# board.net
KiCad netlist of a schematic drawn in EAGLE
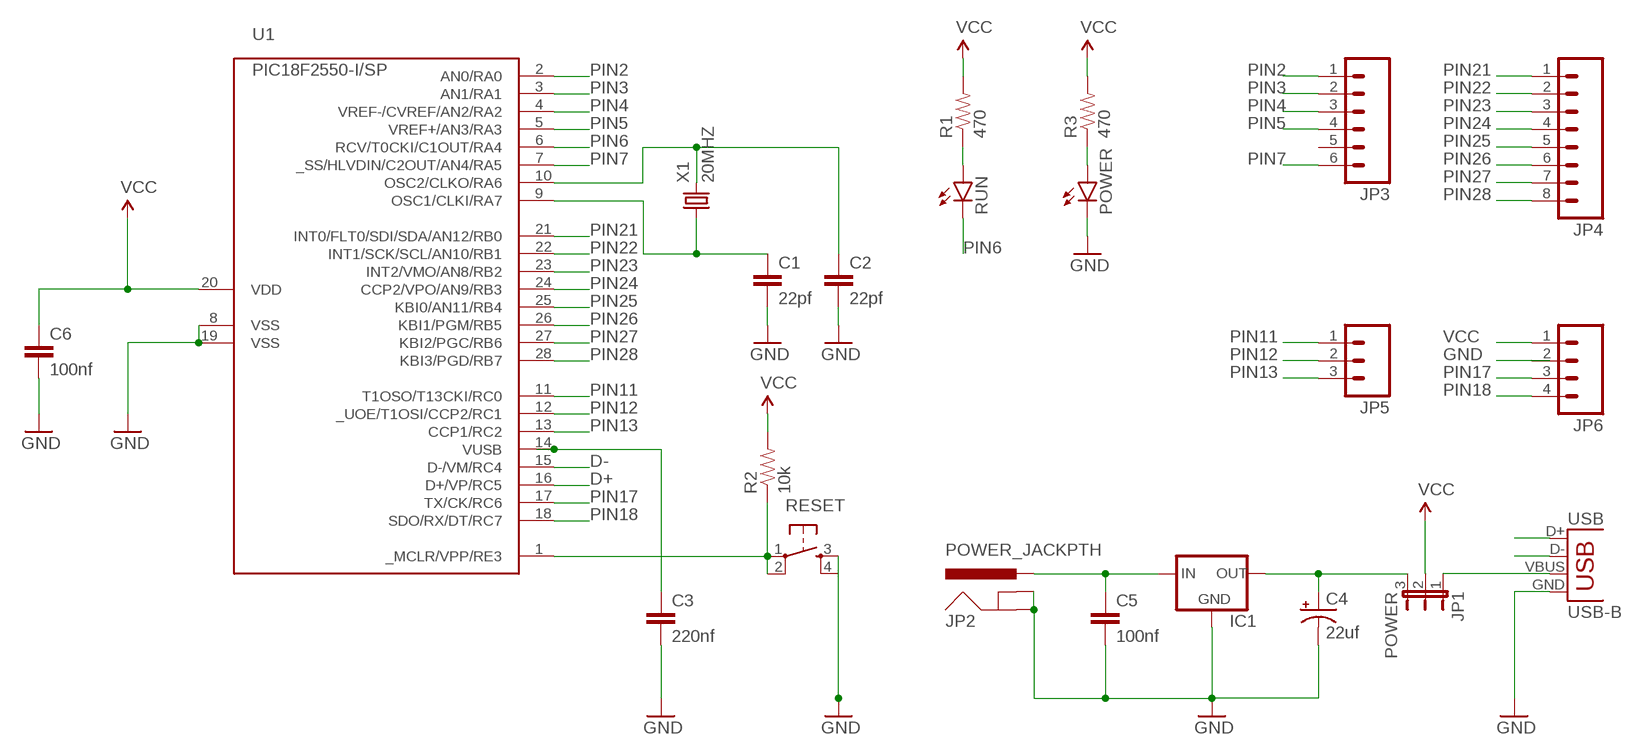
[diagram p0: schematic, sheet 1]

(export (version "E")
  (design (tool "Eeschema 10.0.6"))
  (components
    (comp (ref "C1")
      (value "22pf")
      (footprint "eagle-import:CAP-PTH-SMALL-KIT")
      (libsource (lib "eagle-import") (part "0.1UF-50V-20%(PTH)KIT-EZ"))
    )
    (comp (ref "C2")
      (value "22pf")
      (footprint "eagle-import:CAP-PTH-SMALL-KIT")
      (libsource (lib "eagle-import") (part "0.1UF-50V-20%(PTH)KIT-EZ"))
    )
    (comp (ref "C3")
      (value "220nf")
      (footprint "eagle-import:C050-050X075")
      (libsource (lib "eagle-import") (part "C-EU050-050X075"))
    )
    (comp (ref "C4")
      (value "22uf")
      (footprint "eagle-import:CPOL-RADIAL-10UF-25V-KIT")
      (libsource (lib "eagle-import") (part "10UF-25V-20%(PTH)KIT"))
    )
    (comp (ref "C5")
      (value "100nf")
      (footprint "eagle-import:C050-050X075")
      (libsource (lib "eagle-import") (part "C-EU050-050X075"))
    )
    (comp (ref "C6")
      (value "100nf")
      (footprint "eagle-import:C050-050X075")
      (libsource (lib "eagle-import") (part "C-EU050-050X075"))
    )
    (comp (ref "IC1")
      (value "78XXL")
      (footprint "eagle-import:78XXL")
      (libsource (lib "eagle-import") (part "78XXL"))
    )
    (comp (ref "JP1")
      (value "POWER")
      (footprint "eagle-import:JP2")
      (libsource (lib "eagle-import") (part "JP2E"))
    )
    (comp (ref "JP2")
      (value "POWER_JACKPTH")
      (footprint "eagle-import:POWER_JACK_PTH")
      (libsource (lib "eagle-import") (part "POWER_JACKPTH"))
    )
    (comp (ref "JP3")
      (value "M06NO_SILK_YES_STOP")
      (footprint "eagle-import:1X06_NO_SILK_YES_STOP")
      (libsource (lib "eagle-import") (part "M06NO_SILK_YES_STOP"))
    )
    (comp (ref "JP4")
      (value "M08NO_SILK_FEMALE_PTH")
      (footprint "eagle-import:1X08_NO_SILK")
      (libsource (lib "eagle-import") (part "M08NO_SILK_FEMALE_PTH"))
    )
    (comp (ref "JP5")
      (value "M031X03_NO_SILK")
      (footprint "eagle-import:1X03_NO_SILK")
      (libsource (lib "eagle-import") (part "M031X03_NO_SILK"))
    )
    (comp (ref "JP6")
      (value "M04NO_SILK_ALL_ROUND")
      (footprint "eagle-import:1X04_NO_SILK_ALL_ROUND")
      (libsource (lib "eagle-import") (part "M04NO_SILK_ALL_ROUND"))
    )
    (comp (ref "POWER")
      (value "LED3MM")
      (footprint "eagle-import:LED3MM")
      (libsource (lib "eagle-import") (part "LED3MM"))
    )
    (comp (ref "R1")
      (value "470")
      (footprint "eagle-import:AXIAL-0.4")
      (libsource (lib "eagle-import") (part "RESISTORPTH-1/4W"))
    )
    (comp (ref "R2")
      (value "10k")
      (footprint "eagle-import:AXIAL-0.4")
      (libsource (lib "eagle-import") (part "RESISTORPTH-1/4W"))
    )
    (comp (ref "R3")
      (value "470")
      (footprint "eagle-import:AXIAL-0.4")
      (libsource (lib "eagle-import") (part "RESISTORPTH-1/4W"))
    )
    (comp (ref "RESET")
      (value "TAC_SWITCHPTH")
      (footprint "eagle-import:TACTILE-PTH")
      (libsource (lib "eagle-import") (part "TAC_SWITCHPTH"))
    )
    (comp (ref "RUN")
      (value "LED3MM")
      (footprint "eagle-import:LED3MM")
      (libsource (lib "eagle-import") (part "LED3MM"))
    )
    (comp (ref "U1")
      (value "PIC18F2550-I/SP")
      (footprint "eagle-import:DIL28-3")
      (libsource (lib "eagle-import") (part "PIC182550-I/SPF"))
    )
    (comp (ref "USB")
      (value "USB-B")
      (footprint "eagle-import:USB-B-PTH")
      (libsource (lib "eagle-import") (part "USBPTH"))
    )
    (comp (ref "X1")
      (value "20MHZ")
      (footprint "eagle-import:HC49")
      (libsource (lib "eagle-import") (part "CRYSTALS-NOGND-HC49"))
    )
  )
  (nets
    (net (code "1") (name "/D+") (class "Default")
      (node (ref "U1") (pin "16") (pinfunction "D+/VP/RC5_16") (pintype "bidirectional"))
      (node (ref "USB") (pin "D+") (pinfunction "D+_D+") (pintype "bidirectional"))
    )
    (net (code "2") (name "/D-") (class "Default")
      (node (ref "U1") (pin "15") (pinfunction "D-/VM/RC4_15") (pintype "bidirectional"))
      (node (ref "USB") (pin "D-") (pinfunction "D-_D-") (pintype "bidirectional"))
    )
    (net (code "3") (name "/PIN2") (class "Default")
      (node (ref "JP3") (pin "1") (pinfunction "1_1") (pintype "passive"))
      (node (ref "U1") (pin "2") (pinfunction "AN0/RA0_2") (pintype "bidirectional"))
    )
    (net (code "4") (name "/PIN3") (class "Default")
      (node (ref "JP3") (pin "2") (pinfunction "2_2") (pintype "passive"))
      (node (ref "U1") (pin "3") (pinfunction "AN1/RA1_3") (pintype "bidirectional"))
    )
    (net (code "5") (name "/PIN4") (class "Default")
      (node (ref "JP3") (pin "3") (pinfunction "3_3") (pintype "passive"))
      (node (ref "U1") (pin "4") (pinfunction "VREF-/CVREF/AN2/RA2_4") (pintype "bidirectional"))
    )
    (net (code "6") (name "/PIN5") (class "Default")
      (node (ref "JP3") (pin "4") (pinfunction "4_4") (pintype "passive"))
      (node (ref "U1") (pin "5") (pinfunction "VREF+/AN3/RA3_5") (pintype "bidirectional"))
    )
    (net (code "7") (name "/PIN6") (class "Default")
      (node (ref "RUN") (pin "K") (pinfunction "C_K") (pintype "passive"))
      (node (ref "U1") (pin "6") (pinfunction "RCV/T0CKI/C1OUT/RA4_6") (pintype "bidirectional"))
    )
    (net (code "8") (name "/PIN7") (class "Default")
      (node (ref "JP3") (pin "6") (pinfunction "6_6") (pintype "passive"))
      (node (ref "U1") (pin "7") (pinfunction "_SS/HLVDIN/C2OUT/AN4/RA5_7") (pintype "bidirectional"))
    )
    (net (code "9") (name "/PIN11") (class "Default")
      (node (ref "JP5") (pin "1") (pinfunction "1_1") (pintype "passive"))
      (node (ref "U1") (pin "11") (pinfunction "T1OSO/T13CKI/RC0_11") (pintype "bidirectional"))
    )
    (net (code "10") (name "/PIN12") (class "Default")
      (node (ref "JP5") (pin "2") (pinfunction "2_2") (pintype "passive"))
      (node (ref "U1") (pin "12") (pinfunction "_UOE/T1OSI/CCP2/RC1_12") (pintype "bidirectional"))
    )
    (net (code "11") (name "/PIN13") (class "Default")
      (node (ref "JP5") (pin "3") (pinfunction "3_3") (pintype "passive"))
      (node (ref "U1") (pin "13") (pinfunction "CCP1/RC2_13") (pintype "bidirectional"))
    )
    (net (code "12") (name "/PIN17") (class "Default")
      (node (ref "JP6") (pin "3") (pinfunction "3_3") (pintype "passive"))
      (node (ref "U1") (pin "17") (pinfunction "TX/CK/RC6_17") (pintype "bidirectional"))
    )
    (net (code "13") (name "/PIN18") (class "Default")
      (node (ref "JP6") (pin "4") (pinfunction "4_4") (pintype "passive"))
      (node (ref "U1") (pin "18") (pinfunction "SDO/RX/DT/RC7_18") (pintype "bidirectional"))
    )
    (net (code "14") (name "/PIN21") (class "Default")
      (node (ref "JP4") (pin "1") (pinfunction "1_1") (pintype "passive"))
      (node (ref "U1") (pin "21") (pinfunction "INT0/FLT0/SDI/SDA/AN12/RB0_21") (pintype "bidirectional"))
    )
    (net (code "15") (name "/PIN22") (class "Default")
      (node (ref "JP4") (pin "2") (pinfunction "2_2") (pintype "passive"))
      (node (ref "U1") (pin "22") (pinfunction "INT1/SCK/SCL/AN10/RB1_22") (pintype "bidirectional"))
    )
    (net (code "16") (name "/PIN23") (class "Default")
      (node (ref "JP4") (pin "3") (pinfunction "3_3") (pintype "passive"))
      (node (ref "U1") (pin "23") (pinfunction "INT2/VMO/AN8/RB2_23") (pintype "bidirectional"))
    )
    (net (code "17") (name "/PIN24") (class "Default")
      (node (ref "JP4") (pin "4") (pinfunction "4_4") (pintype "passive"))
      (node (ref "U1") (pin "24") (pinfunction "CCP2/VPO/AN9/RB3_24") (pintype "bidirectional"))
    )
    (net (code "18") (name "/PIN25") (class "Default")
      (node (ref "JP4") (pin "5") (pinfunction "5_5") (pintype "passive"))
      (node (ref "U1") (pin "25") (pinfunction "KBI0/AN11/RB4_25") (pintype "bidirectional"))
    )
    (net (code "19") (name "/PIN26") (class "Default")
      (node (ref "JP4") (pin "6") (pinfunction "6_6") (pintype "passive"))
      (node (ref "U1") (pin "26") (pinfunction "KBI1/PGM/RB5_26") (pintype "bidirectional"))
    )
    (net (code "20") (name "/PIN27") (class "Default")
      (node (ref "JP4") (pin "7") (pinfunction "7_7") (pintype "passive"))
      (node (ref "U1") (pin "27") (pinfunction "KBI2/PGC/RB6_27") (pintype "bidirectional"))
    )
    (net (code "21") (name "/PIN28") (class "Default")
      (node (ref "JP4") (pin "8") (pinfunction "8_8") (pintype "passive"))
      (node (ref "U1") (pin "28") (pinfunction "KBI3/PGD/RB7_28") (pintype "bidirectional"))
    )
    (net (code "22") (name "GND") (class "Default")
      (node (ref "C1") (pin "2") (pinfunction "2_2") (pintype "passive"))
      (node (ref "C2") (pin "2") (pinfunction "2_2") (pintype "passive"))
      (node (ref "C3") (pin "2") (pinfunction "2_2") (pintype "passive"))
      (node (ref "C4") (pin "2") (pinfunction "-_2") (pintype "passive"))
      (node (ref "C5") (pin "2") (pinfunction "2_2") (pintype "passive"))
      (node (ref "C6") (pin "2") (pinfunction "2_2") (pintype "passive"))
      (node (ref "IC1") (pin "GND") (pinfunction "GND_GND") (pintype "input"))
      (node (ref "JP2") (pin "GND") (pinfunction "GND_GND") (pintype "bidirectional"))
      (node (ref "JP2") (pin "GNDBREAK") (pinfunction "GNDBREAK_GNDBREAK") (pintype "bidirectional"))
      (node (ref "POWER") (pin "K") (pinfunction "C_K") (pintype "passive"))
      (node (ref "RESET") (pin "3") (pinfunction "3_3") (pintype "passive"))
      (node (ref "RESET") (pin "4") (pinfunction "4_4") (pintype "passive"))
      (node (ref "U1") (pin "19") (pinfunction "VSS_19") (pintype "power_in"))
      (node (ref "U1") (pin "8") (pinfunction "VSS_8") (pintype "power_in"))
      (node (ref "USB") (pin "GND") (pinfunction "GND_GND") (pintype "bidirectional"))
    )
    (net (code "23") (name "Net-(C4-+)") (class "Default")
      (node (ref "C4") (pin "1") (pinfunction "+_1") (pintype "passive"))
      (node (ref "IC1") (pin "OUT") (pinfunction "OUT_OUT") (pintype "passive"))
      (node (ref "JP1") (pin "3") (pinfunction "3_3") (pintype "passive"))
    )
    (net (code "24") (name "Net-(C5-Pad1)") (class "Default")
      (node (ref "C5") (pin "1") (pinfunction "1_1") (pintype "passive"))
      (node (ref "IC1") (pin "IN") (pinfunction "IN_IN") (pintype "input"))
      (node (ref "JP2") (pin "PWR") (pinfunction "PWR_PWR") (pintype "bidirectional"))
    )
    (net (code "25") (name "Net-(JP1-Pad1)") (class "Default")
      (node (ref "JP1") (pin "1") (pinfunction "1_1") (pintype "passive"))
      (node (ref "USB") (pin "VBUS") (pinfunction "VBUS_VBUS") (pintype "bidirectional"))
    )
    (net (code "26") (name "Net-(R1-1)") (class "Default")
      (node (ref "R1") (pin "P$1") (pinfunction "1_P$1") (pintype "passive"))
      (node (ref "RUN") (pin "A") (pinfunction "A_A") (pintype "passive"))
    )
    (net (code "27") (name "Net-(R2-1)") (class "Default")
      (node (ref "R2") (pin "P$1") (pinfunction "1_P$1") (pintype "passive"))
      (node (ref "RESET") (pin "1") (pinfunction "1_1") (pintype "passive"))
      (node (ref "RESET") (pin "2") (pinfunction "2_2") (pintype "passive"))
      (node (ref "U1") (pin "1") (pinfunction "_MCLR/VPP/RE3_1") (pintype "input"))
    )
    (net (code "28") (name "Net-(R3-1)") (class "Default")
      (node (ref "POWER") (pin "A") (pinfunction "A_A") (pintype "passive"))
      (node (ref "R3") (pin "P$1") (pinfunction "1_P$1") (pintype "passive"))
    )
    (net (code "29") (name "Net-(U1-OSC1{slash}CLKI{slash}RA7)") (class "Default")
      (node (ref "C1") (pin "1") (pinfunction "1_1") (pintype "passive"))
      (node (ref "U1") (pin "9") (pinfunction "OSC1/CLKI/RA7_9") (pintype "bidirectional"))
      (node (ref "X1") (pin "1") (pinfunction "1_1") (pintype "passive"))
    )
    (net (code "30") (name "Net-(U1-OSC2{slash}CLKO{slash}RA6)") (class "Default")
      (node (ref "C2") (pin "1") (pinfunction "1_1") (pintype "passive"))
      (node (ref "U1") (pin "10") (pinfunction "OSC2/CLKO/RA6_10") (pintype "bidirectional"))
      (node (ref "X1") (pin "2") (pinfunction "2_2") (pintype "passive"))
    )
    (net (code "31") (name "Net-(U1-VUSB)") (class "Default")
      (node (ref "C3") (pin "1") (pinfunction "1_1") (pintype "passive"))
      (node (ref "U1") (pin "14") (pinfunction "VUSB_14") (pintype "bidirectional"))
    )
    (net (code "32") (name "VCC") (class "Default")
      (node (ref "C6") (pin "1") (pinfunction "1_1") (pintype "passive"))
      (node (ref "JP1") (pin "2") (pinfunction "2_2") (pintype "passive"))
      (node (ref "JP6") (pin "1") (pinfunction "1_1") (pintype "passive"))
      (node (ref "R1") (pin "P$2") (pinfunction "2_P$2") (pintype "passive"))
      (node (ref "R2") (pin "P$2") (pinfunction "2_P$2") (pintype "passive"))
      (node (ref "R3") (pin "P$2") (pinfunction "2_P$2") (pintype "passive"))
      (node (ref "U1") (pin "20") (pinfunction "VDD_20") (pintype "power_in"))
    )
    (net (code "33") (name "unconnected-(JP3-Pad5)") (class "Default")
      (node (ref "JP3") (pin "5") (pinfunction "5_5") (pintype "passive"))
    )
    (net (code "34") (name "unconnected-(JP6-Pad2)") (class "Default")
      (node (ref "JP6") (pin "2") (pinfunction "2_2") (pintype "passive"))
    )
  )
)
